# SCH_Power-sequnecing.net
KiCad netlist of a schematic drawn in EasyEDA
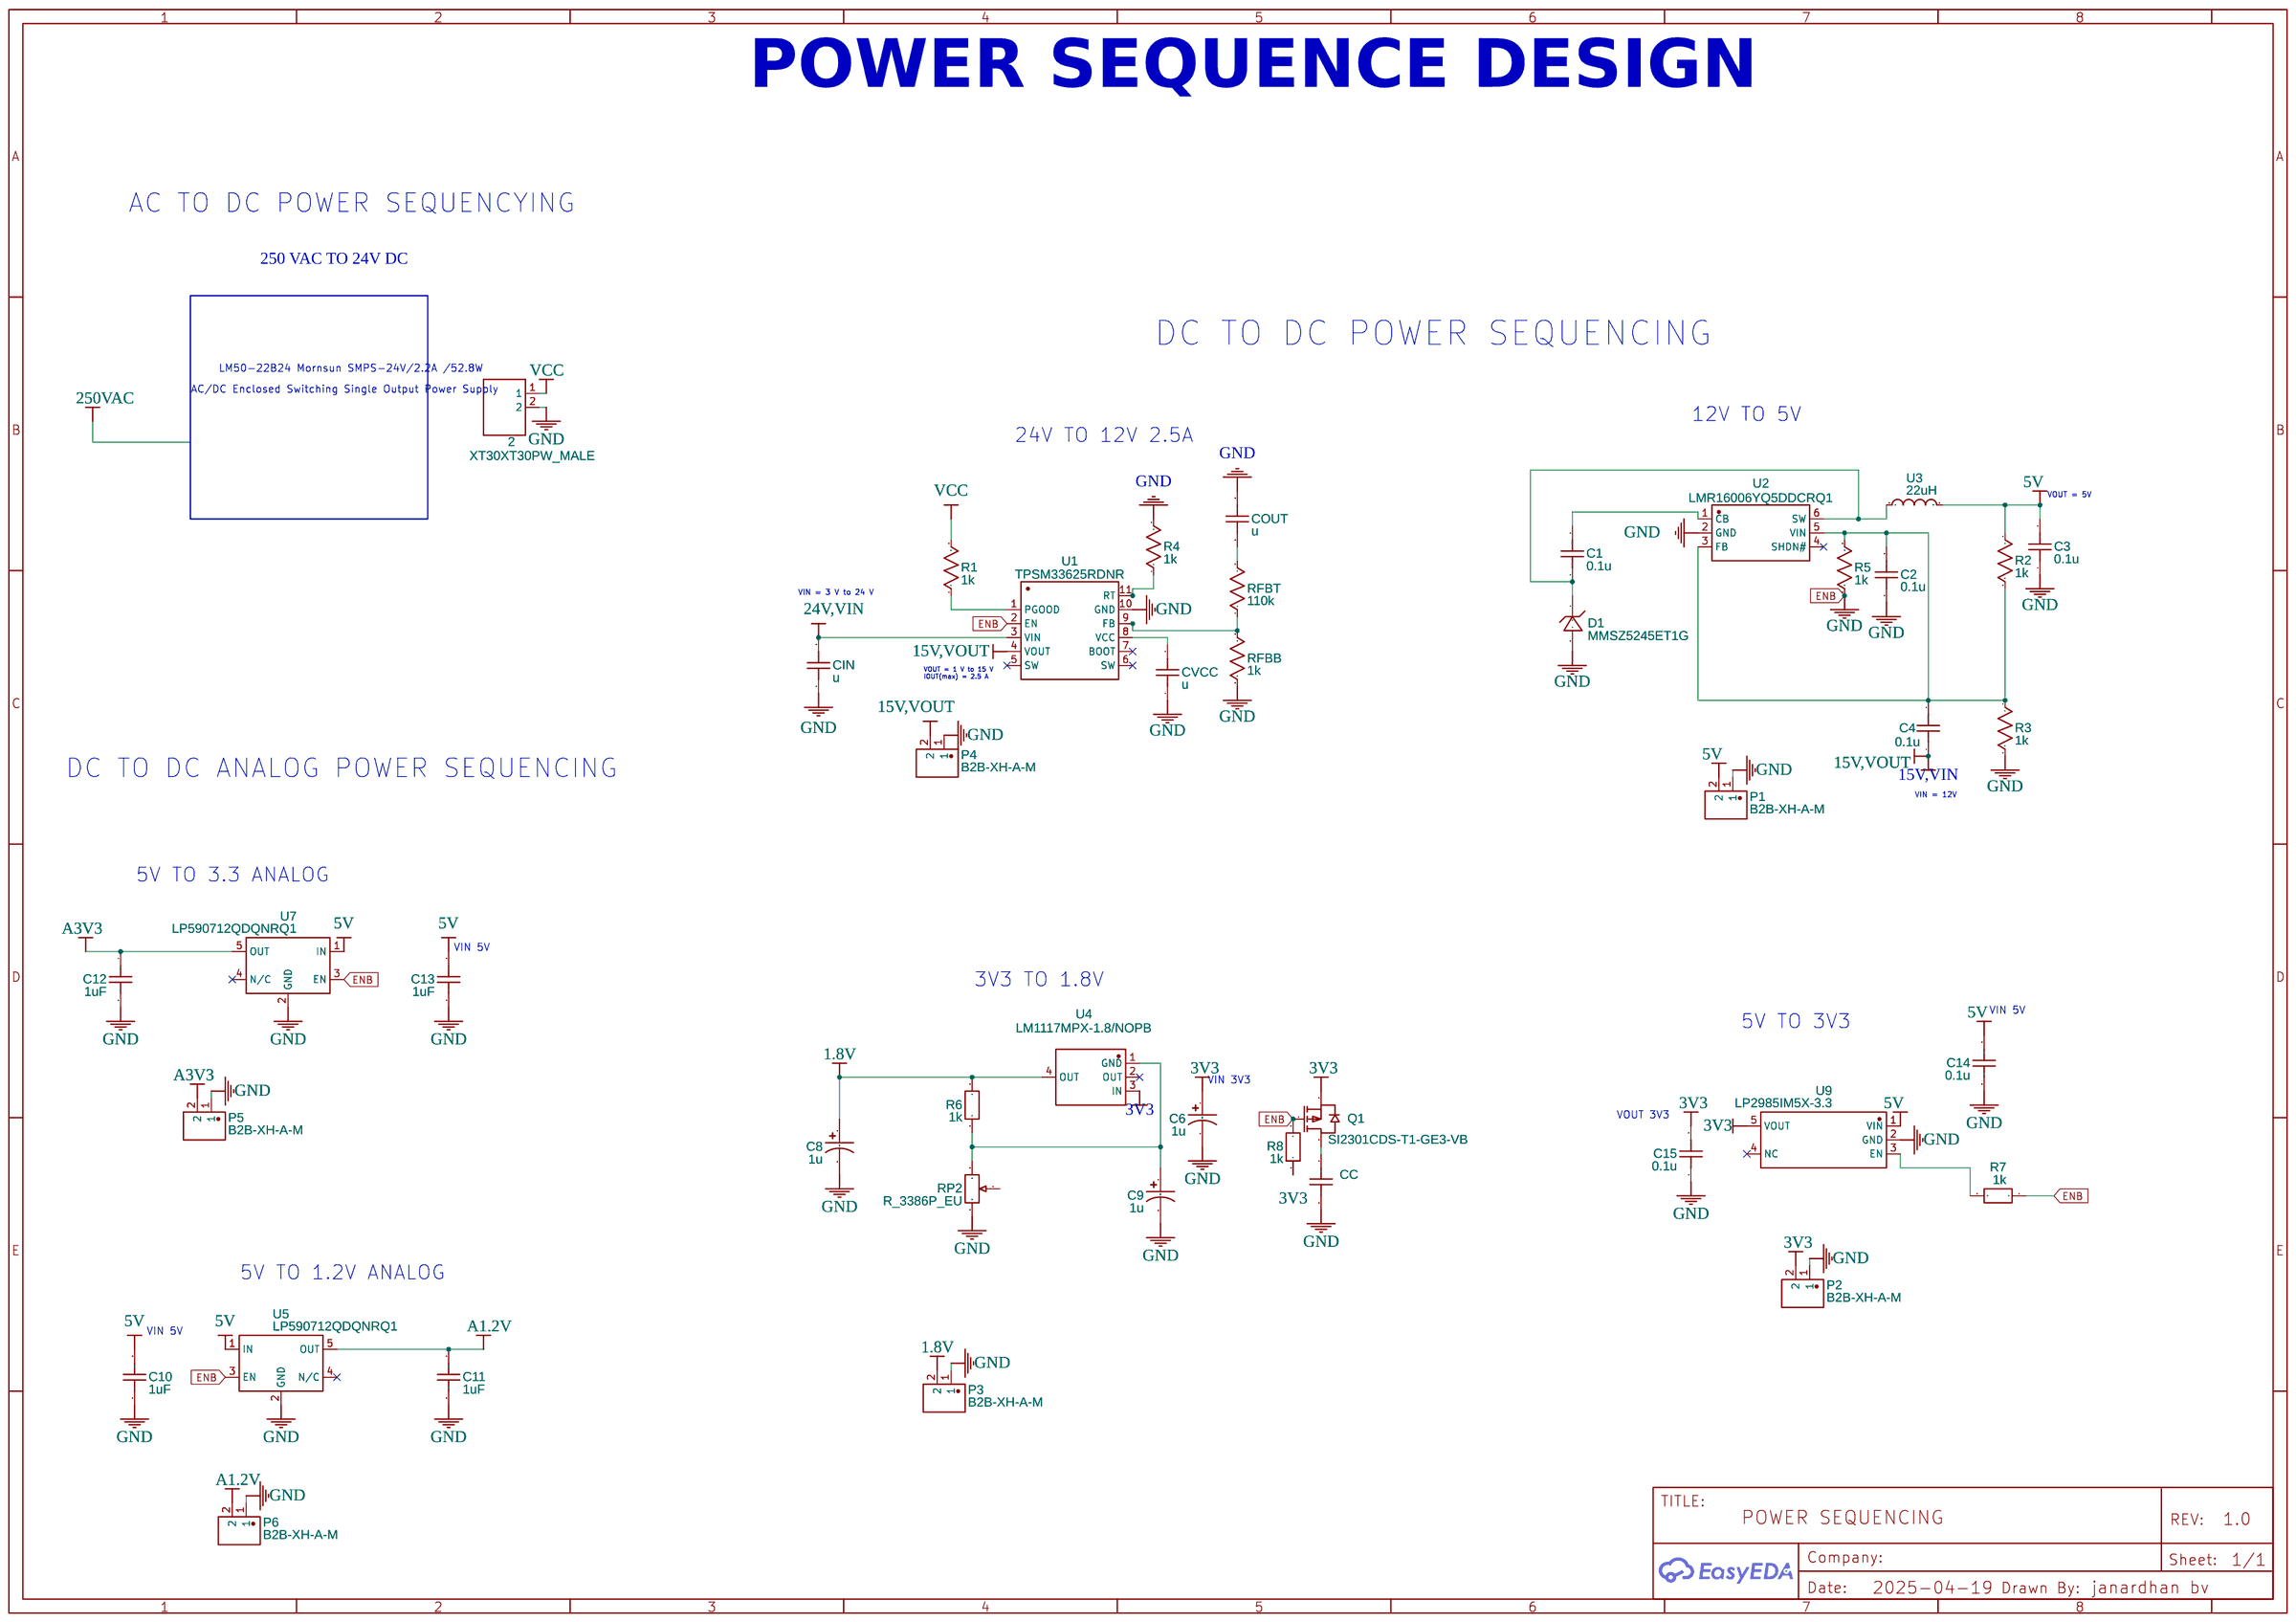
[diagram p0: schematic sheet]

(export (version "E")
  (design (tool "Eeschema 10.0.6"))
  (components
    (comp (ref "2") (value "XT30XT30PW_MALE") (libsource (lib "") (part "XT30XT30PW_MALE")))
    (comp (ref "C1") (value "0.1u") (libsource (lib "") (part "C_0603_US_2")))
    (comp (ref "C2") (value "0.1u") (libsource (lib "") (part "C_0603_US_2")))
    (comp (ref "C3") (value "0.1u") (libsource (lib "") (part "C_0603_US_2")))
    (comp (ref "C4") (value "0.1u") (libsource (lib "") (part "C_0603_US_2")))
    (comp (ref "C6") (value "1u") (libsource (lib "") (part "C_Tan_SMD_A_US")))
    (comp (ref "C8") (value "1u") (libsource (lib "") (part "C_Tan_SMD_A_US")))
    (comp (ref "C9") (value "1u") (libsource (lib "") (part "C_Tan_SMD_A_US")))
    (comp (ref "C10") (value "1uF") (libsource (lib "") (part "C_0603_US_2")))
    (comp (ref "C11") (value "1uF") (libsource (lib "") (part "C_0603_US_5")))
    (comp (ref "C12") (value "1uF") (libsource (lib "") (part "C_0603_US")))
    (comp (ref "C13") (value "1uF") (libsource (lib "") (part "C_0603_US_6")))
    (comp (ref "C14") (value "0.1u") (libsource (lib "") (part "C_0603_US")))
    (comp (ref "C15") (value "0.1u") (libsource (lib "") (part "C_0603_US_6")))
    (comp (ref "CC") (value "0.1u") (libsource (lib "") (part "C_0603_US_3")))
    (comp (ref "CIN") (value "u") (libsource (lib "") (part "C_0603_US_4")))
    (comp (ref "COUT") (value "u") (libsource (lib "") (part "C_0603_US_7")))
    (comp (ref "CVCC") (value "u") (libsource (lib "") (part "C_0603_US_1")))
    (comp (ref "D1")
      (value "MMSZ5245ET1G")
      (fields (field (name "Manufacturer") "onsemi(安森美)"))
      (libsource (lib "") (part "MMSZ5245ET1G"))
    )
    (comp (ref "P1")
      (value "B2B-XH-A-M")
      (fields
        (field (name "Manufacturer Part") "B2B-XH-A-MB2P-VH（SMT业务专用）")
        (field (name "Manufacturer") "JST")
      )
      (libsource (lib "") (part "B2B-XH-A-M"))
    )
    (comp (ref "P2")
      (value "B2B-XH-A-M")
      (fields
        (field (name "Manufacturer Part") "B2B-XH-A-MB2P-VH（SMT业务专用）")
        (field (name "Manufacturer") "JST")
      )
      (libsource (lib "") (part "B2B-XH-A-M"))
    )
    (comp (ref "P3")
      (value "B2B-XH-A-M")
      (fields
        (field (name "Manufacturer Part") "B2B-XH-A-MB2P-VH（SMT业务专用）")
        (field (name "Manufacturer") "JST")
      )
      (libsource (lib "") (part "B2B-XH-A-M"))
    )
    (comp (ref "P4")
      (value "B2B-XH-A-M")
      (fields
        (field (name "Manufacturer Part") "B2B-XH-A-MB2P-VH（SMT业务专用）")
        (field (name "Manufacturer") "JST")
      )
      (libsource (lib "") (part "B2B-XH-A-M"))
    )
    (comp (ref "P5")
      (value "B2B-XH-A-M")
      (fields
        (field (name "Manufacturer Part") "B2B-XH-A-MB2P-VH（SMT业务专用）")
        (field (name "Manufacturer") "JST")
      )
      (libsource (lib "") (part "B2B-XH-A-M"))
    )
    (comp (ref "P6")
      (value "B2B-XH-A-M")
      (fields
        (field (name "Manufacturer Part") "B2B-XH-A-MB2P-VH（SMT业务专用）")
        (field (name "Manufacturer") "JST")
      )
      (libsource (lib "") (part "B2B-XH-A-M"))
    )
    (comp (ref "Q1")
      (value "SI2301CDS-T1-GE3-VB")
      (fields (field (name "Manufacturer") "VBsemi(微碧半导体)"))
      (libsource (lib "") (part "SI2301CDS-T1-GE3-VB"))
    )
    (comp (ref "R1") (value "1k") (libsource (lib "") (part "R_0603_US")))
    (comp (ref "R2") (value "1k") (libsource (lib "") (part "R_0603_US_3")))
    (comp (ref "R3") (value "1k") (libsource (lib "") (part "R_0603_US_3")))
    (comp (ref "R4") (value "1k") (libsource (lib "") (part "R_0603_US")))
    (comp (ref "R5") (value "1k") (libsource (lib "") (part "R_0603_US")))
    (comp (ref "R6") (value "1k") (libsource (lib "") (part "R_0603_EU")))
    (comp (ref "R7") (value "1k") (libsource (lib "") (part "R_0603_EU_1")))
    (comp (ref "R8") (value "1k") (libsource (lib "") (part "R_0603_EU")))
    (comp (ref "RFBB") (value "1k") (libsource (lib "") (part "R_0603_US_2")))
    (comp (ref "RFBT") (value "110k") (libsource (lib "") (part "R_0603_US_1")))
    (comp (ref "RP2") (value "R_3386P_EU") (libsource (lib "") (part "R_3386P_EU")))
    (comp (ref "U1")
      (value "TPSM33625RDNR")
      (fields (field (name "Manufacturer") "TI(德州仪器)"))
      (libsource (lib "") (part "TPSM33625RDNR"))
    )
    (comp (ref "U2")
      (value "LMR16006YQ5DDCRQ1")
      (fields (field (name "Manufacturer") "TI(德州仪器)"))
      (libsource (lib "") (part "LMR16006YQ5DDCRQ1"))
    )
    (comp (ref "U3")
      (value "22uH")
      (fields
        (field (name "Manufacturer Part") "SNR.201610.SYB220MT00")
        (field (name "Manufacturer") "SOREDE(索瑞达)")
      )
      (libsource (lib "") (part "SNR.201610.SYB220MT00"))
    )
    (comp (ref "U4")
      (value "LM1117MPX-1.8/NOPB")
      (fields (field (name "Manufacturer") "TI(德州仪器)"))
      (libsource (lib "") (part "LM1117MPX-1.8/NOPB"))
    )
    (comp (ref "U5")
      (value "LP590712QDQNRQ1")
      (fields
        (field (name "Manufacturer Part") "LP5907MFX-1.8/NOPB")
        (field (name "Manufacturer") "TI(德州仪器)")
      )
      (libsource (lib "") (part "LP5907MFX-1.8/NOPB_1"))
    )
    (comp (ref "U7")
      (value "LP590712QDQNRQ1")
      (fields
        (field (name "Manufacturer Part") "LP5907MFX-1.8/NOPB")
        (field (name "Manufacturer") "TI(德州仪器)")
      )
      (libsource (lib "") (part "LP5907MFX-1.8/NOPB"))
    )
    (comp (ref "U9")
      (value "LP2985IM5X-3.3")
      (fields (field (name "Manufacturer") "TECH PUBLIC(台舟)"))
      (libsource (lib "") (part "LP2985IM5X-3.3"))
    )
  )
  (nets
    (net (code "1") (name "1.8V") (class "Default")
      (node (ref "C8") (pin "1") (pinfunction "1_1") (pintype "unspecified"))
      (node (ref "P3") (pin "2") (pinfunction "2_2") (pintype "unspecified"))
      (node (ref "R6") (pin "2") (pinfunction "2_2") (pintype "unspecified"))
      (node (ref "U4") (pin "4") (pinfunction "OUT_4") (pintype "unspecified"))
    )
    (net (code "2") (name "3V3") (class "Default")
      (node (ref "C15") (pin "2") (pinfunction "2_2") (pintype "unspecified"))
      (node (ref "C6") (pin "1") (pinfunction "1_1") (pintype "unspecified"))
      (node (ref "P2") (pin "2") (pinfunction "2_2") (pintype "unspecified"))
      (node (ref "Q1") (pin "2") (pinfunction "S_2") (pintype "unspecified"))
      (node (ref "R8") (pin "1") (pinfunction "1_1") (pintype "unspecified"))
      (node (ref "U4") (pin "3") (pinfunction "IN_3") (pintype "unspecified"))
      (node (ref "U9") (pin "5") (pinfunction "VOUT_5") (pintype "unspecified"))
    )
    (net (code "3") (name "5V") (class "Default")
      (node (ref "C10") (pin "2") (pinfunction "2_2") (pintype "unspecified"))
      (node (ref "C13") (pin "2") (pinfunction "2_2") (pintype "unspecified"))
      (node (ref "C14") (pin "1") (pinfunction "1_1") (pintype "unspecified"))
      (node (ref "C3") (pin "2") (pinfunction "2_2") (pintype "unspecified"))
      (node (ref "P1") (pin "2") (pinfunction "2_2") (pintype "unspecified"))
      (node (ref "R2") (pin "1") (pinfunction "1_1") (pintype "unspecified"))
      (node (ref "U3") (pin "2") (pinfunction "2_2") (pintype "unspecified"))
      (node (ref "U5") (pin "1") (pinfunction "IN_1") (pintype "unspecified"))
      (node (ref "U7") (pin "1") (pinfunction "IN_1") (pintype "unspecified"))
      (node (ref "U9") (pin "1") (pinfunction "VIN_1") (pintype "unspecified"))
    )
    (net (code "4") (name "15V,VIN") (class "Default")
      (node (ref "C4") (pin "1") (pinfunction "1_1") (pintype "unspecified"))
      (node (ref "P4") (pin "2") (pinfunction "2_2") (pintype "unspecified"))
      (node (ref "U1") (pin "4") (pinfunction "VOUT_4") (pintype "unspecified"))
    )
    (net (code "5") (name "24V,VIN") (class "Default")
      (node (ref "CIN") (pin "2") (pinfunction "2_2") (pintype "unspecified"))
      (node (ref "U1") (pin "3") (pinfunction "VIN_3") (pintype "unspecified"))
    )
    (net (code "7") (name "A1.2V") (class "Default")
      (node (ref "C11") (pin "1") (pinfunction "1_1") (pintype "unspecified"))
      (node (ref "P6") (pin "2") (pinfunction "2_2") (pintype "unspecified"))
      (node (ref "U5") (pin "5") (pinfunction "OUT_5") (pintype "unspecified"))
    )
    (net (code "8") (name "A3V3") (class "Default")
      (node (ref "C12") (pin "1") (pinfunction "1_1") (pintype "unspecified"))
      (node (ref "P5") (pin "2") (pinfunction "2_2") (pintype "unspecified"))
      (node (ref "U7") (pin "5") (pinfunction "OUT_5") (pintype "unspecified"))
    )
    (net (code "9") (name "ENB") (class "Default")
      (node (ref "2") (pin "2") (pinfunction "2_2") (pintype "bidirectional"))
      (node (ref "C10") (pin "1") (pinfunction "1_1") (pintype "unspecified"))
      (node (ref "C11") (pin "2") (pinfunction "2_2") (pintype "unspecified"))
      (node (ref "C12") (pin "2") (pinfunction "2_2") (pintype "unspecified"))
      (node (ref "C13") (pin "1") (pinfunction "1_1") (pintype "unspecified"))
      (node (ref "C14") (pin "2") (pinfunction "2_2") (pintype "unspecified"))
      (node (ref "C15") (pin "1") (pinfunction "1_1") (pintype "unspecified"))
      (node (ref "C2") (pin "1") (pinfunction "1_1") (pintype "unspecified"))
      (node (ref "C3") (pin "1") (pinfunction "1_1") (pintype "unspecified"))
      (node (ref "C6") (pin "2") (pinfunction "2_2") (pintype "unspecified"))
      (node (ref "C8") (pin "2") (pinfunction "2_2") (pintype "unspecified"))
      (node (ref "C9") (pin "2") (pinfunction "2_2") (pintype "unspecified"))
      (node (ref "CC") (pin "2") (pinfunction "2_2") (pintype "unspecified"))
      (node (ref "CIN") (pin "1") (pinfunction "1_1") (pintype "unspecified"))
      (node (ref "COUT") (pin "1") (pinfunction "1_1") (pintype "unspecified"))
      (node (ref "CVCC") (pin "1") (pinfunction "1_1") (pintype "unspecified"))
      (node (ref "D1") (pin "2") (pinfunction "A_2") (pintype "unspecified"))
      (node (ref "P1") (pin "1") (pinfunction "1_1") (pintype "unspecified"))
      (node (ref "P2") (pin "1") (pinfunction "1_1") (pintype "unspecified"))
      (node (ref "P3") (pin "1") (pinfunction "1_1") (pintype "unspecified"))
      (node (ref "P4") (pin "1") (pinfunction "1_1") (pintype "unspecified"))
      (node (ref "P5") (pin "1") (pinfunction "1_1") (pintype "unspecified"))
      (node (ref "P6") (pin "1") (pinfunction "1_1") (pintype "unspecified"))
      (node (ref "Q1") (pin "1") (pinfunction "G_1") (pintype "unspecified"))
      (node (ref "R3") (pin "2") (pinfunction "2_2") (pintype "unspecified"))
      (node (ref "R4") (pin "2") (pinfunction "2_2") (pintype "unspecified"))
      (node (ref "R5") (pin "1") (pinfunction "1_1") (pintype "unspecified"))
      (node (ref "R7") (pin "1") (pinfunction "1_1") (pintype "unspecified"))
      (node (ref "R8") (pin "2") (pinfunction "2_2") (pintype "unspecified"))
      (node (ref "RFBB") (pin "2") (pinfunction "2_2") (pintype "unspecified"))
      (node (ref "RP2") (pin "1") (pinfunction "1_1") (pintype "input"))
      (node (ref "U1") (pin "10") (pinfunction "GND_10") (pintype "unspecified"))
      (node (ref "U1") (pin "2") (pinfunction "EN_2") (pintype "unspecified"))
      (node (ref "U2") (pin "2") (pinfunction "GND_2") (pintype "unspecified"))
      (node (ref "U5") (pin "2") (pinfunction "GND_2") (pintype "unspecified"))
      (node (ref "U5") (pin "3") (pinfunction "EN_3") (pintype "unspecified"))
      (node (ref "U7") (pin "2") (pinfunction "GND_2") (pintype "unspecified"))
      (node (ref "U7") (pin "3") (pinfunction "EN_3") (pintype "unspecified"))
      (node (ref "U9") (pin "2") (pinfunction "GND_2") (pintype "unspecified"))
    )
    (net (code "10") (name "Net-(COUT-Pad2)") (class "Default")
      (node (ref "COUT") (pin "2") (pinfunction "2_2") (pintype "unspecified"))
      (node (ref "RFBT") (pin "2") (pinfunction "2_2") (pintype "unspecified"))
    )
    (net (code "11") (name "Net-(D1-C)") (class "Default")
      (node (ref "C1") (pin "1") (pinfunction "1_1") (pintype "unspecified"))
      (node (ref "D1") (pin "1") (pinfunction "C_1") (pintype "unspecified"))
      (node (ref "U2") (pin "6") (pinfunction "SW_6") (pintype "unspecified"))
      (node (ref "U3") (pin "1") (pinfunction "1_1") (pintype "unspecified"))
    )
    (net (code "12") (name "Net-(Q1-D)") (class "Default")
      (node (ref "CC") (pin "1") (pinfunction "1_1") (pintype "unspecified"))
      (node (ref "Q1") (pin "3") (pinfunction "D_3") (pintype "unspecified"))
    )
    (net (code "13") (name "Net-(U1-FB)") (class "Default")
      (node (ref "RFBB") (pin "1") (pinfunction "1_1") (pintype "unspecified"))
      (node (ref "RFBT") (pin "1") (pinfunction "1_1") (pintype "unspecified"))
      (node (ref "U1") (pin "9") (pinfunction "FB_9") (pintype "unspecified"))
    )
    (net (code "14") (name "Net-(U1-PGOOD)") (class "Default")
      (node (ref "R1") (pin "1") (pinfunction "1_1") (pintype "unspecified"))
      (node (ref "U1") (pin "1") (pinfunction "PGOOD_1") (pintype "unspecified"))
    )
    (net (code "15") (name "Net-(U1-RT)") (class "Default")
      (node (ref "R4") (pin "1") (pinfunction "1_1") (pintype "unspecified"))
      (node (ref "U1") (pin "11") (pinfunction "RT_11") (pintype "unspecified"))
    )
    (net (code "16") (name "Net-(U1-VCC)") (class "Default")
      (node (ref "CVCC") (pin "2") (pinfunction "2_2") (pintype "unspecified"))
      (node (ref "U1") (pin "8") (pinfunction "VCC_8") (pintype "unspecified"))
    )
    (net (code "17") (name "Net-(U2-CB)") (class "Default")
      (node (ref "C1") (pin "2") (pinfunction "2_2") (pintype "unspecified"))
      (node (ref "U2") (pin "1") (pinfunction "CB_1") (pintype "unspecified"))
    )
    (net (code "18") (name "Net-(U2-FB)") (class "Default")
      (node (ref "C2") (pin "2") (pinfunction "2_2") (pintype "unspecified"))
      (node (ref "C4") (pin "2") (pinfunction "2_2") (pintype "unspecified"))
      (node (ref "R2") (pin "2") (pinfunction "2_2") (pintype "unspecified"))
      (node (ref "R3") (pin "1") (pinfunction "1_1") (pintype "unspecified"))
      (node (ref "R5") (pin "2") (pinfunction "2_2") (pintype "unspecified"))
      (node (ref "U2") (pin "3") (pinfunction "FB_3") (pintype "unspecified"))
      (node (ref "U2") (pin "5") (pinfunction "VIN_5") (pintype "unspecified"))
    )
    (net (code "19") (name "Net-(U4-GND)") (class "Default")
      (node (ref "C9") (pin "1") (pinfunction "1_1") (pintype "unspecified"))
      (node (ref "R6") (pin "1") (pinfunction "1_1") (pintype "unspecified"))
      (node (ref "RP2") (pin "3") (pinfunction "3_3") (pintype "input"))
      (node (ref "U4") (pin "1") (pinfunction "GND_1") (pintype "unspecified"))
    )
    (net (code "20") (name "Net-(U9-EN)") (class "Default")
      (node (ref "R7") (pin "2") (pinfunction "2_2") (pintype "unspecified"))
      (node (ref "U9") (pin "3") (pinfunction "EN_3") (pintype "unspecified"))
    )
    (net (code "21") (name "VCC") (class "Default")
      (node (ref "2") (pin "1") (pinfunction "1_1") (pintype "bidirectional"))
      (node (ref "R1") (pin "2") (pinfunction "2_2") (pintype "unspecified"))
    )
    (net (code "22") (name "unconnected-(RP2-Pad2)") (class "Default")
      (node (ref "RP2") (pin "2") (pinfunction "2_2") (pintype "input"))
    )
    (net (code "23") (name "unconnected-(U1-BOOT-Pad7)") (class "Default")
      (node (ref "U1") (pin "7") (pinfunction "BOOT_7") (pintype "unspecified+no_connect"))
    )
    (net (code "24") (name "unconnected-(U1-SW-Pad5)") (class "Default")
      (node (ref "U1") (pin "5") (pinfunction "SW_5") (pintype "unspecified+no_connect"))
    )
    (net (code "25") (name "unconnected-(U1-SW-Pad6)") (class "Default")
      (node (ref "U1") (pin "6") (pinfunction "SW_6") (pintype "unspecified+no_connect"))
    )
    (net (code "26") (name "unconnected-(U2-SHDN#-Pad4)") (class "Default")
      (node (ref "U2") (pin "4") (pinfunction "SHDN#_4") (pintype "unspecified+no_connect"))
    )
    (net (code "27") (name "unconnected-(U4-OUT-Pad2)") (class "Default")
      (node (ref "U4") (pin "2") (pinfunction "OUT_2") (pintype "unspecified+no_connect"))
    )
    (net (code "28") (name "unconnected-(U5-N{slash}C-Pad4)") (class "Default")
      (node (ref "U5") (pin "4") (pinfunction "N/C_4") (pintype "unspecified+no_connect"))
    )
    (net (code "29") (name "unconnected-(U7-N{slash}C-Pad4)") (class "Default")
      (node (ref "U7") (pin "4") (pinfunction "N/C_4") (pintype "unspecified+no_connect"))
    )
    (net (code "30") (name "unconnected-(U9-NC-Pad4)") (class "Default")
      (node (ref "U9") (pin "4") (pinfunction "NC_4") (pintype "unspecified+no_connect"))
    )
  )
)
